# Amstrad-CPC-2855-PIO-Test-1-0.net
KiCad netlist of a schematic drawn in EAGLE
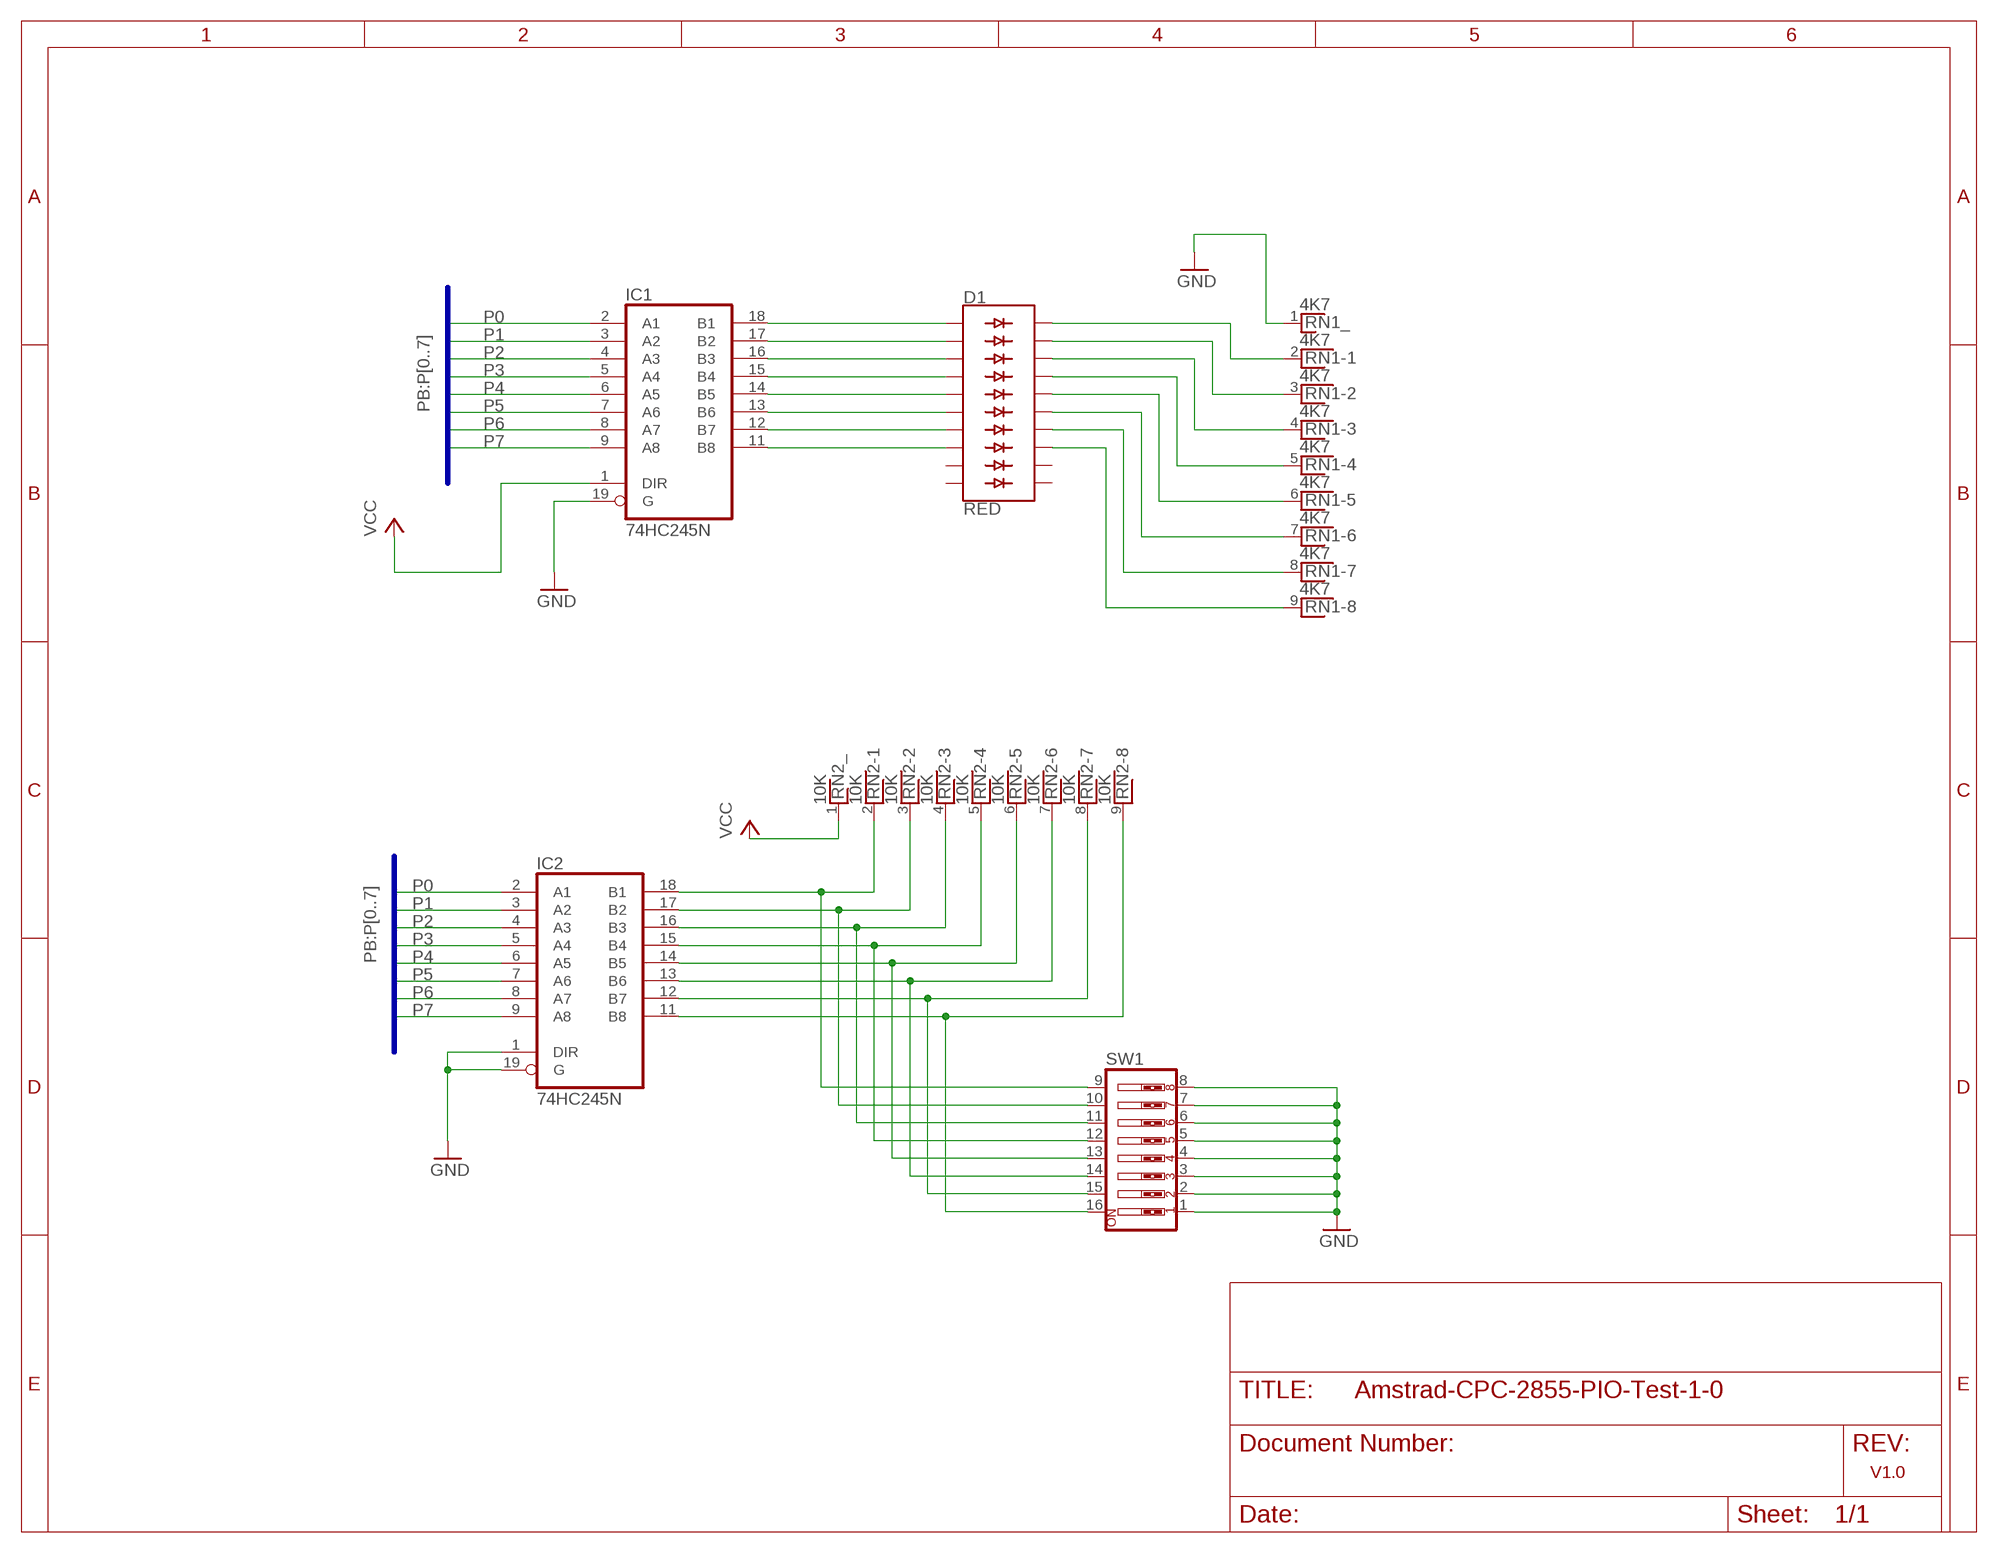
[diagram p0: schematic, sheet 1]

(export (version "E")
  (design (tool "Eeschema 10.0.6"))
  (components
    (comp (ref "D1")
      (value "RED")
      (footprint "eagle-import:LED_BARGRAPH_10")
      (libsource (lib "eagle-import") (part "LED_BARGRAPH_10RED"))
    )
    (comp (ref "IC1")
      (value "74HC245N")
      (footprint "eagle-import:DIL20")
      (libsource (lib "eagle-import") (part "74245NHC"))
    )
    (comp (ref "IC2")
      (value "74HC245N")
      (footprint "eagle-import:DIL20")
      (libsource (lib "eagle-import") (part "74245NHC"))
    )
    (comp (ref "RN1")
      (value "4K7")
      (footprint "eagle-import:RN-9")
      (libsource (lib "eagle-import") (part "RNX8"))
    )
    (comp (ref "RN2")
      (value "10K")
      (footprint "eagle-import:RN-9")
      (libsource (lib "eagle-import") (part "RNX8"))
    )
    (comp (ref "SW1")
      (value "SW_DIP-8")
      (footprint "eagle-import:EDG-08")
      (libsource (lib "eagle-import") (part "SW_DIP-8"))
    )
  )
  (nets
    (net (code "9") (name "/P0") (class "Default")
      (node (ref "IC1") (pin "2") (pinfunction "A1_2") (pintype "bidirectional"))
      (node (ref "IC2") (pin "2") (pinfunction "A1_2") (pintype "bidirectional"))
    )
    (net (code "10") (name "/P1") (class "Default")
      (node (ref "IC1") (pin "3") (pinfunction "A2_3") (pintype "bidirectional"))
      (node (ref "IC2") (pin "3") (pinfunction "A2_3") (pintype "bidirectional"))
    )
    (net (code "11") (name "/P2") (class "Default")
      (node (ref "IC1") (pin "4") (pinfunction "A3_4") (pintype "bidirectional"))
      (node (ref "IC2") (pin "4") (pinfunction "A3_4") (pintype "bidirectional"))
    )
    (net (code "12") (name "/P3") (class "Default")
      (node (ref "IC1") (pin "5") (pinfunction "A4_5") (pintype "bidirectional"))
      (node (ref "IC2") (pin "5") (pinfunction "A4_5") (pintype "bidirectional"))
    )
    (net (code "13") (name "/P4") (class "Default")
      (node (ref "IC1") (pin "6") (pinfunction "A5_6") (pintype "bidirectional"))
      (node (ref "IC2") (pin "6") (pinfunction "A5_6") (pintype "bidirectional"))
    )
    (net (code "14") (name "/P5") (class "Default")
      (node (ref "IC1") (pin "7") (pinfunction "A6_7") (pintype "bidirectional"))
      (node (ref "IC2") (pin "7") (pinfunction "A6_7") (pintype "bidirectional"))
    )
    (net (code "15") (name "/P6") (class "Default")
      (node (ref "IC1") (pin "8") (pinfunction "A7_8") (pintype "bidirectional"))
      (node (ref "IC2") (pin "8") (pinfunction "A7_8") (pintype "bidirectional"))
    )
    (net (code "16") (name "/P7") (class "Default")
      (node (ref "IC1") (pin "9") (pinfunction "A8_9") (pintype "bidirectional"))
      (node (ref "IC2") (pin "9") (pinfunction "A8_9") (pintype "bidirectional"))
    )
    (net (code "18") (name "GND") (class "Default")
      (node (ref "IC1") (pin "19") (pinfunction "G_19") (pintype "input"))
      (node (ref "IC2") (pin "1") (pinfunction "DIR_1") (pintype "input"))
      (node (ref "IC2") (pin "19") (pinfunction "G_19") (pintype "input"))
      (node (ref "RN1") (pin "1") (pinfunction "1_1") (pintype "passive"))
      (node (ref "SW1") (pin "1") (pinfunction "1_1") (pintype "passive"))
      (node (ref "SW1") (pin "2") (pinfunction "2_2") (pintype "passive"))
      (node (ref "SW1") (pin "3") (pinfunction "3_3") (pintype "passive"))
      (node (ref "SW1") (pin "4") (pinfunction "4_4") (pintype "passive"))
      (node (ref "SW1") (pin "5") (pinfunction "5_5") (pintype "passive"))
      (node (ref "SW1") (pin "6") (pinfunction "6_6") (pintype "passive"))
      (node (ref "SW1") (pin "7") (pinfunction "7_7") (pintype "passive"))
      (node (ref "SW1") (pin "8") (pinfunction "8_8") (pintype "passive"))
    )
    (net (code "19") (name "Net-(D1-A)") (class "Default")
      (node (ref "D1") (pin "1") (pinfunction "A_1") (pintype "passive"))
      (node (ref "IC1") (pin "18") (pinfunction "B1_18") (pintype "bidirectional"))
    )
    (net (code "20") (name "Net-(D1-A1)") (class "Default")
      (node (ref "D1") (pin "2") (pinfunction "A1_2") (pintype "passive"))
      (node (ref "IC1") (pin "17") (pinfunction "B2_17") (pintype "bidirectional"))
    )
    (net (code "21") (name "Net-(D1-A2)") (class "Default")
      (node (ref "D1") (pin "3") (pinfunction "A2_3") (pintype "passive"))
      (node (ref "IC1") (pin "16") (pinfunction "B3_16") (pintype "bidirectional"))
    )
    (net (code "22") (name "Net-(D1-A3)") (class "Default")
      (node (ref "D1") (pin "4") (pinfunction "A3_4") (pintype "passive"))
      (node (ref "IC1") (pin "15") (pinfunction "B4_15") (pintype "bidirectional"))
    )
    (net (code "23") (name "Net-(D1-A4)") (class "Default")
      (node (ref "D1") (pin "5") (pinfunction "A4_5") (pintype "passive"))
      (node (ref "IC1") (pin "14") (pinfunction "B5_14") (pintype "bidirectional"))
    )
    (net (code "24") (name "Net-(D1-A5)") (class "Default")
      (node (ref "D1") (pin "6") (pinfunction "A5_6") (pintype "passive"))
      (node (ref "IC1") (pin "13") (pinfunction "B6_13") (pintype "bidirectional"))
    )
    (net (code "25") (name "Net-(D1-A6)") (class "Default")
      (node (ref "D1") (pin "7") (pinfunction "A6_7") (pintype "passive"))
      (node (ref "IC1") (pin "12") (pinfunction "B7_12") (pintype "bidirectional"))
    )
    (net (code "26") (name "Net-(D1-A7)") (class "Default")
      (node (ref "D1") (pin "8") (pinfunction "A7_8") (pintype "passive"))
      (node (ref "IC1") (pin "11") (pinfunction "B8_11") (pintype "bidirectional"))
    )
    (net (code "27") (name "Net-(D1-C)") (class "Default")
      (node (ref "D1") (pin "20") (pinfunction "C_20") (pintype "passive"))
      (node (ref "RN1") (pin "2") (pinfunction "1_2") (pintype "passive"))
    )
    (net (code "28") (name "Net-(D1-C1)") (class "Default")
      (node (ref "D1") (pin "19") (pinfunction "C1_19") (pintype "passive"))
      (node (ref "RN1") (pin "3") (pinfunction "1_3") (pintype "passive"))
    )
    (net (code "29") (name "Net-(D1-C2)") (class "Default")
      (node (ref "D1") (pin "18") (pinfunction "C2_18") (pintype "passive"))
      (node (ref "RN1") (pin "4") (pinfunction "1_4") (pintype "passive"))
    )
    (net (code "30") (name "Net-(D1-C3)") (class "Default")
      (node (ref "D1") (pin "17") (pinfunction "C3_17") (pintype "passive"))
      (node (ref "RN1") (pin "5") (pinfunction "1_5") (pintype "passive"))
    )
    (net (code "31") (name "Net-(D1-C4)") (class "Default")
      (node (ref "D1") (pin "16") (pinfunction "C4_16") (pintype "passive"))
      (node (ref "RN1") (pin "6") (pinfunction "1_6") (pintype "passive"))
    )
    (net (code "32") (name "Net-(D1-C5)") (class "Default")
      (node (ref "D1") (pin "15") (pinfunction "C5_15") (pintype "passive"))
      (node (ref "RN1") (pin "7") (pinfunction "1_7") (pintype "passive"))
    )
    (net (code "33") (name "Net-(D1-C6)") (class "Default")
      (node (ref "D1") (pin "14") (pinfunction "C6_14") (pintype "passive"))
      (node (ref "RN1") (pin "8") (pinfunction "1_8") (pintype "passive"))
    )
    (net (code "34") (name "Net-(D1-C7)") (class "Default")
      (node (ref "D1") (pin "13") (pinfunction "C7_13") (pintype "passive"))
      (node (ref "RN1") (pin "9") (pinfunction "1_9") (pintype "passive"))
    )
    (net (code "35") (name "Net-(IC2A-B1)") (class "Default")
      (node (ref "IC2") (pin "18") (pinfunction "B1_18") (pintype "bidirectional"))
      (node (ref "RN2") (pin "2") (pinfunction "1_2") (pintype "passive"))
      (node (ref "SW1") (pin "9") (pinfunction "9_9") (pintype "passive"))
    )
    (net (code "36") (name "Net-(IC2A-B2)") (class "Default")
      (node (ref "IC2") (pin "17") (pinfunction "B2_17") (pintype "bidirectional"))
      (node (ref "RN2") (pin "3") (pinfunction "1_3") (pintype "passive"))
      (node (ref "SW1") (pin "10") (pinfunction "10_10") (pintype "passive"))
    )
    (net (code "37") (name "Net-(IC2A-B3)") (class "Default")
      (node (ref "IC2") (pin "16") (pinfunction "B3_16") (pintype "bidirectional"))
      (node (ref "RN2") (pin "4") (pinfunction "1_4") (pintype "passive"))
      (node (ref "SW1") (pin "11") (pinfunction "11_11") (pintype "passive"))
    )
    (net (code "38") (name "Net-(IC2A-B4)") (class "Default")
      (node (ref "IC2") (pin "15") (pinfunction "B4_15") (pintype "bidirectional"))
      (node (ref "RN2") (pin "5") (pinfunction "1_5") (pintype "passive"))
      (node (ref "SW1") (pin "12") (pinfunction "12_12") (pintype "passive"))
    )
    (net (code "39") (name "Net-(IC2A-B5)") (class "Default")
      (node (ref "IC2") (pin "14") (pinfunction "B5_14") (pintype "bidirectional"))
      (node (ref "RN2") (pin "6") (pinfunction "1_6") (pintype "passive"))
      (node (ref "SW1") (pin "13") (pinfunction "13_13") (pintype "passive"))
    )
    (net (code "40") (name "Net-(IC2A-B6)") (class "Default")
      (node (ref "IC2") (pin "13") (pinfunction "B6_13") (pintype "bidirectional"))
      (node (ref "RN2") (pin "7") (pinfunction "1_7") (pintype "passive"))
      (node (ref "SW1") (pin "14") (pinfunction "14_14") (pintype "passive"))
    )
    (net (code "41") (name "Net-(IC2A-B7)") (class "Default")
      (node (ref "IC2") (pin "12") (pinfunction "B7_12") (pintype "bidirectional"))
      (node (ref "RN2") (pin "8") (pinfunction "1_8") (pintype "passive"))
      (node (ref "SW1") (pin "15") (pinfunction "15_15") (pintype "passive"))
    )
    (net (code "42") (name "Net-(IC2A-B8)") (class "Default")
      (node (ref "IC2") (pin "11") (pinfunction "B8_11") (pintype "bidirectional"))
      (node (ref "RN2") (pin "9") (pinfunction "1_9") (pintype "passive"))
      (node (ref "SW1") (pin "16") (pinfunction "16_16") (pintype "passive"))
    )
    (net (code "43") (name "VCC") (class "Default")
      (node (ref "IC1") (pin "1") (pinfunction "DIR_1") (pintype "input"))
      (node (ref "RN2") (pin "1") (pinfunction "1_1") (pintype "passive"))
    )
    (net (code "44") (name "unconnected-(D1-A8-Pad9)") (class "Default")
      (node (ref "D1") (pin "9") (pinfunction "A8_9") (pintype "passive"))
    )
    (net (code "45") (name "unconnected-(D1-A9-Pad10)") (class "Default")
      (node (ref "D1") (pin "10") (pinfunction "A9_10") (pintype "passive"))
    )
    (net (code "46") (name "unconnected-(D1-C8-Pad12)") (class "Default")
      (node (ref "D1") (pin "12") (pinfunction "C8_12") (pintype "passive"))
    )
    (net (code "47") (name "unconnected-(D1-C9-Pad11)") (class "Default")
      (node (ref "D1") (pin "11") (pinfunction "C9_11") (pintype "passive"))
    )
  )
)
